# matchbox_cpu_v10.net
KiCad netlist of a schematic drawn in EAGLE
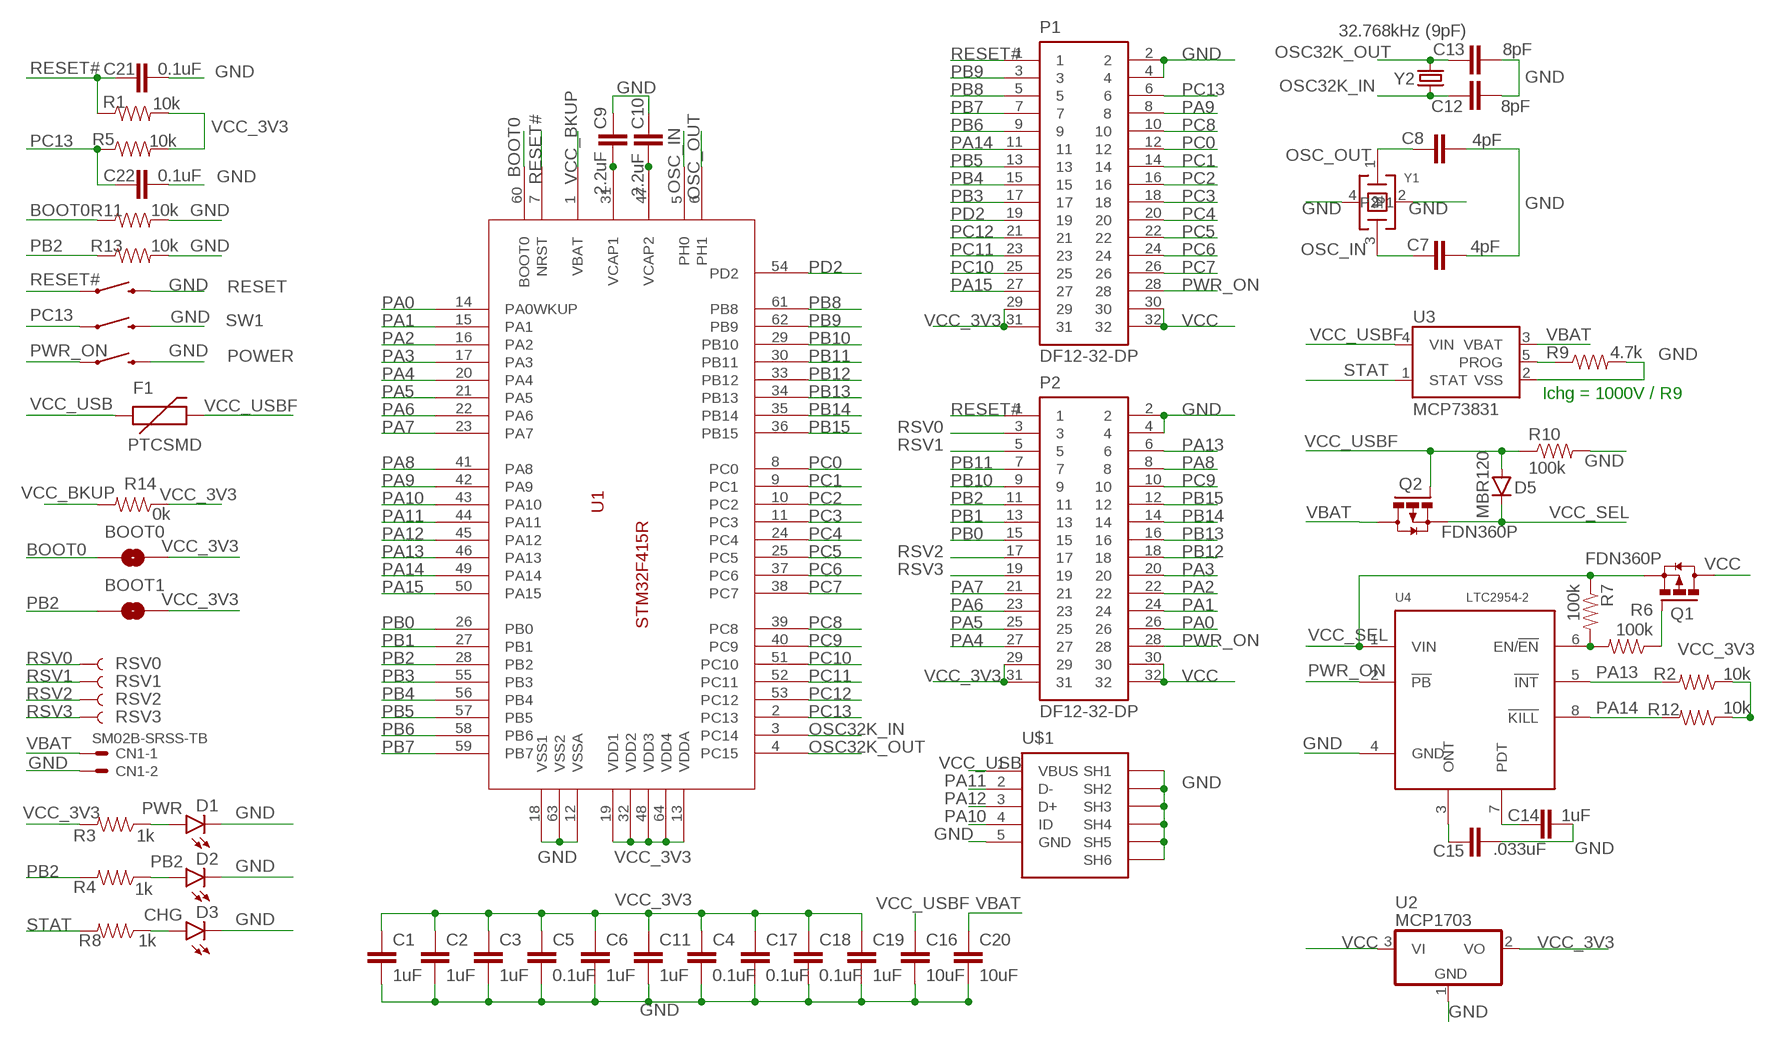
[diagram p0: schematic, sheet 1]

(export (version "E")
  (design (tool "Eeschema 10.0.6"))
  (components
    (comp (ref "BOOT0")
      (value "JUMPER-PAD-2-NOYES_SILK")
      (footprint "eagle-import:PAD-JUMPER-2-NO_YES_SILK")
      (libsource (lib "eagle-import") (part "JUMPER-PAD-2-NOYES_SILK"))
    )
    (comp (ref "BOOT1")
      (value "JUMPER-PAD-2-NOYES_SILK")
      (footprint "eagle-import:PAD-JUMPER-2-NO_YES_SILK")
      (libsource (lib "eagle-import") (part "JUMPER-PAD-2-NOYES_SILK"))
    )
    (comp (ref "C1")
      (value "1uF")
      (footprint "eagle-import:0805")
      (libsource (lib "eagle-import") (part "CAP0805"))
    )
    (comp (ref "C2")
      (value "1uF")
      (footprint "eagle-import:0805")
      (libsource (lib "eagle-import") (part "CAP0805"))
    )
    (comp (ref "C3")
      (value "1uF")
      (footprint "eagle-import:0805")
      (libsource (lib "eagle-import") (part "CAP0805"))
    )
    (comp (ref "C4")
      (value "0.1uF")
      (footprint "eagle-import:0805")
      (libsource (lib "eagle-import") (part "CAP0805"))
    )
    (comp (ref "C5")
      (value "0.1uF")
      (footprint "eagle-import:0805")
      (libsource (lib "eagle-import") (part "CAP0805"))
    )
    (comp (ref "C6")
      (value "1uF")
      (footprint "eagle-import:0805")
      (libsource (lib "eagle-import") (part "CAP0805"))
    )
    (comp (ref "C7")
      (value "4pF")
      (footprint "eagle-import:0805")
      (libsource (lib "eagle-import") (part "CAP0805"))
    )
    (comp (ref "C8")
      (value "4pF")
      (footprint "eagle-import:0805")
      (libsource (lib "eagle-import") (part "CAP0805"))
    )
    (comp (ref "C9")
      (value "2.2uF")
      (footprint "eagle-import:0805")
      (libsource (lib "eagle-import") (part "CAP0805"))
    )
    (comp (ref "C10")
      (value "2.2uF")
      (footprint "eagle-import:0805")
      (libsource (lib "eagle-import") (part "CAP0805"))
    )
    (comp (ref "C11")
      (value "1uF")
      (footprint "eagle-import:0805")
      (libsource (lib "eagle-import") (part "CAP0805"))
    )
    (comp (ref "C12")
      (value "8pF")
      (footprint "eagle-import:0402-CAP")
      (libsource (lib "eagle-import") (part "CAP0402-CAP"))
    )
    (comp (ref "C13")
      (value "8pF")
      (footprint "eagle-import:0402-CAP")
      (libsource (lib "eagle-import") (part "CAP0402-CAP"))
    )
    (comp (ref "C14")
      (value "1uF")
      (footprint "eagle-import:0805")
      (libsource (lib "eagle-import") (part "CAP0805"))
    )
    (comp (ref "C15")
      (value ".033uF")
      (footprint "eagle-import:0805")
      (libsource (lib "eagle-import") (part "CAP0805"))
    )
    (comp (ref "C16")
      (value "10uF")
      (footprint "eagle-import:0805")
      (libsource (lib "eagle-import") (part "CAP0805"))
    )
    (comp (ref "C17")
      (value "0.1uF")
      (footprint "eagle-import:0805")
      (libsource (lib "eagle-import") (part "CAP0805"))
    )
    (comp (ref "C18")
      (value "0.1uF")
      (footprint "eagle-import:0805")
      (libsource (lib "eagle-import") (part "CAP0805"))
    )
    (comp (ref "C19")
      (value "1uF")
      (footprint "eagle-import:0805")
      (libsource (lib "eagle-import") (part "CAP0805"))
    )
    (comp (ref "C20")
      (value "10uF")
      (footprint "eagle-import:0805")
      (libsource (lib "eagle-import") (part "CAP0805"))
    )
    (comp (ref "C21")
      (value "0.1uF")
      (footprint "eagle-import:0805")
      (libsource (lib "eagle-import") (part "CAP0805"))
    )
    (comp (ref "C22")
      (value "0.1uF")
      (footprint "eagle-import:0805")
      (libsource (lib "eagle-import") (part "CAP0805"))
    )
    (comp (ref "CN1")
      (value "SM02B-SRSS-TB")
      (footprint "eagle-import:SM02B-SRSS-TB")
      (libsource (lib "eagle-import") (part "?M02B-SRSS-TBS"))
    )
    (comp (ref "D1")
      (value "PWR")
      (footprint "eagle-import:LED-0603")
      (libsource (lib "eagle-import") (part "LED0603"))
    )
    (comp (ref "D2")
      (value "PB2")
      (footprint "eagle-import:LED-0603")
      (libsource (lib "eagle-import") (part "LED0603"))
    )
    (comp (ref "D3")
      (value "CHG")
      (footprint "eagle-import:LED-0603")
      (libsource (lib "eagle-import") (part "LED0603"))
    )
    (comp (ref "D5")
      (value "MBR120")
      (footprint "eagle-import:SOD-123")
      (libsource (lib "eagle-import") (part "DIODESOD123"))
    )
    (comp (ref "F1")
      (value "PTCSMD")
      (footprint "eagle-import:PTC-1206")
      (libsource (lib "eagle-import") (part "PTCSMD"))
    )
    (comp (ref "P1")
      (value "DF12-32-DP")
      (footprint "eagle-import:DF12-32-DP")
      (fields (field (name "PARTNO") "AS-ITM-00015"))
      (libsource (lib "eagle-import") (part "AS-ITM-00015"))
    )
    (comp (ref "P2")
      (value "DF12-32-DP")
      (footprint "eagle-import:DF12-32-DP")
      (fields (field (name "PARTNO") "AS-ITM-00015"))
      (libsource (lib "eagle-import") (part "AS-ITM-00015"))
    )
    (comp (ref "POWER")
      (value "SWITCH-MOMENTARY-2SMD-REDUNDANT")
      (footprint "eagle-import:TACTILE-SWITCH-SMD")
      (libsource (lib "eagle-import") (part "SWITCH-MOMENTARY-2SMD-REDUNDANT"))
    )
    (comp (ref "Q1")
      (value "FDN360P")
      (footprint "eagle-import:SUPER-SOT3")
      (libsource (lib "eagle-import") (part "FDN360P"))
    )
    (comp (ref "Q2")
      (value "FDN360P")
      (footprint "eagle-import:SUPER-SOT3")
      (libsource (lib "eagle-import") (part "FDN360P"))
    )
    (comp (ref "R1")
      (value "10k")
      (footprint "eagle-import:0805")
      (libsource (lib "eagle-import") (part "RESISTOR0805-RES"))
    )
    (comp (ref "R2")
      (value "10k")
      (footprint "eagle-import:0805")
      (libsource (lib "eagle-import") (part "RESISTOR0805-RES"))
    )
    (comp (ref "R3")
      (value "1k")
      (footprint "eagle-import:0805")
      (libsource (lib "eagle-import") (part "RESISTOR0805-RES"))
    )
    (comp (ref "R4")
      (value "1k")
      (footprint "eagle-import:0805")
      (libsource (lib "eagle-import") (part "RESISTOR0805-RES"))
    )
    (comp (ref "R5")
      (value "10k")
      (footprint "eagle-import:0805")
      (libsource (lib "eagle-import") (part "RESISTOR0805-RES"))
    )
    (comp (ref "R6")
      (value "100k")
      (footprint "eagle-import:0805")
      (libsource (lib "eagle-import") (part "RESISTOR0805-RES"))
    )
    (comp (ref "R7")
      (value "100k")
      (footprint "eagle-import:0805")
      (libsource (lib "eagle-import") (part "RESISTOR0805-RES"))
    )
    (comp (ref "R8")
      (value "1k")
      (footprint "eagle-import:0805")
      (libsource (lib "eagle-import") (part "RESISTOR0805-RES"))
    )
    (comp (ref "R9")
      (value "4.7k")
      (footprint "eagle-import:0805")
      (libsource (lib "eagle-import") (part "RESISTOR0805-RES"))
    )
    (comp (ref "R10")
      (value "100k")
      (footprint "eagle-import:0805")
      (libsource (lib "eagle-import") (part "RESISTOR0805-RES"))
    )
    (comp (ref "R11")
      (value "10k")
      (footprint "eagle-import:0805")
      (libsource (lib "eagle-import") (part "RESISTOR0805-RES"))
    )
    (comp (ref "R12")
      (value "10k")
      (footprint "eagle-import:0805")
      (libsource (lib "eagle-import") (part "RESISTOR0805-RES"))
    )
    (comp (ref "R13")
      (value "10k")
      (footprint "eagle-import:0805")
      (libsource (lib "eagle-import") (part "RESISTOR0805-RES"))
    )
    (comp (ref "R14")
      (value "0k")
      (footprint "eagle-import:0805")
      (libsource (lib "eagle-import") (part "RESISTOR0805-RES"))
    )
    (comp (ref "RESET")
      (value "SWITCH-MOMENTARY-2SMD-REDUNDANT")
      (footprint "eagle-import:TACTILE-SWITCH-SMD")
      (libsource (lib "eagle-import") (part "SWITCH-MOMENTARY-2SMD-REDUNDANT"))
    )
    (comp (ref "RSV0")
      (value "TEST-POINT3")
      (footprint "eagle-import:PAD.03X.03")
      (libsource (lib "eagle-import") (part "TEST-POINT3"))
    )
    (comp (ref "RSV1")
      (value "TEST-POINT3")
      (footprint "eagle-import:PAD.03X.03")
      (libsource (lib "eagle-import") (part "TEST-POINT3"))
    )
    (comp (ref "RSV2")
      (value "TEST-POINT3")
      (footprint "eagle-import:PAD.03X.03")
      (libsource (lib "eagle-import") (part "TEST-POINT3"))
    )
    (comp (ref "RSV3")
      (value "TEST-POINT3")
      (footprint "eagle-import:PAD.03X.03")
      (libsource (lib "eagle-import") (part "TEST-POINT3"))
    )
    (comp (ref "SW1")
      (value "SWITCH-MOMENTARY-2SMD-REDUNDANT")
      (footprint "eagle-import:TACTILE-SWITCH-SMD")
      (libsource (lib "eagle-import") (part "SWITCH-MOMENTARY-2SMD-REDUNDANT"))
    )
    (comp (ref "U$1")
      (value "MICROUSB")
      (footprint "eagle-import:MICROUSB")
      (libsource (lib "eagle-import") (part "MICROUSB"))
    )
    (comp (ref "U1")
      (value "STM32F415R")
      (footprint "eagle-import:LQFP64")
      (libsource (lib "eagle-import") (part "STM32F4R_64PIN_FOXCAR"))
    )
    (comp (ref "U2")
      (value "MCP1703")
      (footprint "eagle-import:SOT23A")
      (libsource (lib "eagle-import") (part "MCP1703"))
    )
    (comp (ref "U3")
      (value "MCP73831")
      (footprint "eagle-import:SOT23-5")
      (libsource (lib "eagle-import") (part "MCP73831"))
    )
    (comp (ref "U4")
      (value "LTC2954-2")
      (footprint "eagle-import:SOT23-8")
      (libsource (lib "eagle-import") (part "LTC2954"))
    )
    (comp (ref "Y1")
      (value "16MHz(9pF)")
      (footprint "eagle-import:ABM11")
      (fields (field (name "PARTNO") "AS-ITM-00228"))
      (libsource (lib "eagle-import") (part "AS-ITM-00228"))
    )
    (comp (ref "Y2")
      (value "32.768kHz (9pF)")
      (footprint "eagle-import:CRYSTAL-32KHZ-SMD_EPSON_MC146")
      (libsource (lib "eagle-import") (part "CRYSTALEPSONMC146"))
    )
  )
  (nets
    (net (code "1") (name "/BOOT0") (class "Default")
      (node (ref "BOOT0") (pin "1") (pinfunction "1_1") (pintype "passive"))
      (node (ref "R11") (pin "1") (pinfunction "1_1") (pintype "passive"))
      (node (ref "U1") (pin "60") (pinfunction "BOOT0_60") (pintype "input"))
    )
    (net (code "2") (name "/GND") (class "Default")
      (node (ref "C1") (pin "2") (pinfunction "2_2") (pintype "passive"))
      (node (ref "C10") (pin "1") (pinfunction "1_1") (pintype "passive"))
      (node (ref "C11") (pin "2") (pinfunction "2_2") (pintype "passive"))
      (node (ref "C12") (pin "2") (pinfunction "2_2") (pintype "passive"))
      (node (ref "C13") (pin "2") (pinfunction "2_2") (pintype "passive"))
      (node (ref "C14") (pin "2") (pinfunction "2_2") (pintype "passive"))
      (node (ref "C15") (pin "2") (pinfunction "2_2") (pintype "passive"))
      (node (ref "C16") (pin "2") (pinfunction "2_2") (pintype "passive"))
      (node (ref "C17") (pin "2") (pinfunction "2_2") (pintype "passive"))
      (node (ref "C18") (pin "2") (pinfunction "2_2") (pintype "passive"))
      (node (ref "C19") (pin "2") (pinfunction "2_2") (pintype "passive"))
      (node (ref "C2") (pin "2") (pinfunction "2_2") (pintype "passive"))
      (node (ref "C20") (pin "2") (pinfunction "2_2") (pintype "passive"))
      (node (ref "C21") (pin "2") (pinfunction "2_2") (pintype "passive"))
      (node (ref "C22") (pin "2") (pinfunction "2_2") (pintype "passive"))
      (node (ref "C3") (pin "2") (pinfunction "2_2") (pintype "passive"))
      (node (ref "C4") (pin "2") (pinfunction "2_2") (pintype "passive"))
      (node (ref "C5") (pin "2") (pinfunction "2_2") (pintype "passive"))
      (node (ref "C6") (pin "2") (pinfunction "2_2") (pintype "passive"))
      (node (ref "C7") (pin "2") (pinfunction "2_2") (pintype "passive"))
      (node (ref "C8") (pin "2") (pinfunction "2_2") (pintype "passive"))
      (node (ref "C9") (pin "1") (pinfunction "1_1") (pintype "passive"))
      (node (ref "CN1") (pin "2") (pinfunction "S_2") (pintype "passive"))
      (node (ref "D1") (pin "C") (pinfunction "C_C") (pintype "passive"))
      (node (ref "D2") (pin "C") (pinfunction "C_C") (pintype "passive"))
      (node (ref "D3") (pin "C") (pinfunction "C_C") (pintype "passive"))
      (node (ref "P1") (pin "2") (pinfunction "2_2") (pintype "bidirectional"))
      (node (ref "P1") (pin "4") (pinfunction "4_4") (pintype "bidirectional"))
      (node (ref "P2") (pin "2") (pinfunction "2_2") (pintype "bidirectional"))
      (node (ref "P2") (pin "4") (pinfunction "4_4") (pintype "bidirectional"))
      (node (ref "POWER") (pin "3") (pinfunction "2_3") (pintype "passive"))
      (node (ref "POWER") (pin "4") (pinfunction "2_4") (pintype "passive"))
      (node (ref "R10") (pin "2") (pinfunction "2_2") (pintype "passive"))
      (node (ref "R11") (pin "2") (pinfunction "2_2") (pintype "passive"))
      (node (ref "R13") (pin "2") (pinfunction "2_2") (pintype "passive"))
      (node (ref "R9") (pin "2") (pinfunction "2_2") (pintype "passive"))
      (node (ref "RESET") (pin "3") (pinfunction "2_3") (pintype "passive"))
      (node (ref "RESET") (pin "4") (pinfunction "2_4") (pintype "passive"))
      (node (ref "SW1") (pin "3") (pinfunction "2_3") (pintype "passive"))
      (node (ref "SW1") (pin "4") (pinfunction "2_4") (pintype "passive"))
      (node (ref "U$1") (pin "10") (pinfunction "SH5_10") (pintype "bidirectional"))
      (node (ref "U$1") (pin "11") (pinfunction "SH6_11") (pintype "bidirectional"))
      (node (ref "U$1") (pin "5") (pinfunction "GND_5") (pintype "bidirectional"))
      (node (ref "U$1") (pin "6") (pinfunction "SH1_6") (pintype "bidirectional"))
      (node (ref "U$1") (pin "7") (pinfunction "SH2_7") (pintype "bidirectional"))
      (node (ref "U$1") (pin "8") (pinfunction "SH3_8") (pintype "bidirectional"))
      (node (ref "U$1") (pin "9") (pinfunction "SH4_9") (pintype "bidirectional"))
      (node (ref "U1") (pin "12") (pinfunction "VSSA_12") (pintype "input"))
      (node (ref "U1") (pin "18") (pinfunction "VSS1_18") (pintype "input"))
      (node (ref "U1") (pin "63") (pinfunction "VSS2_63") (pintype "input"))
      (node (ref "U2") (pin "1") (pinfunction "GND_1") (pintype "passive"))
      (node (ref "U3") (pin "2") (pinfunction "VSS_2") (pintype "power_in"))
      (node (ref "U4") (pin "4") (pinfunction "GND_4") (pintype "power_in"))
      (node (ref "Y1") (pin "2") (pinfunction "P2_2") (pintype "bidirectional"))
      (node (ref "Y1") (pin "4") (pinfunction "P1_4") (pintype "bidirectional"))
    )
    (net (code "3") (name "/OSC32K_IN") (class "Default")
      (node (ref "C12") (pin "1") (pinfunction "1_1") (pintype "passive"))
      (node (ref "U1") (pin "3") (pinfunction "PC14_3") (pintype "bidirectional"))
      (node (ref "Y2") (pin "P$2") (pinfunction "1_P$2") (pintype "passive"))
    )
    (net (code "4") (name "/OSC32K_OUT") (class "Default")
      (node (ref "C13") (pin "1") (pinfunction "1_1") (pintype "passive"))
      (node (ref "U1") (pin "4") (pinfunction "PC15_4") (pintype "bidirectional"))
      (node (ref "Y2") (pin "P$1") (pinfunction "2_P$1") (pintype "passive"))
    )
    (net (code "5") (name "/OSC_IN") (class "Default")
      (node (ref "C7") (pin "1") (pinfunction "1_1") (pintype "passive"))
      (node (ref "U1") (pin "5") (pinfunction "PH0_5") (pintype "bidirectional"))
      (node (ref "Y1") (pin "3") (pinfunction "2_3") (pintype "bidirectional"))
    )
    (net (code "6") (name "/OSC_OUT") (class "Default")
      (node (ref "C8") (pin "1") (pinfunction "1_1") (pintype "passive"))
      (node (ref "U1") (pin "6") (pinfunction "PH1_6") (pintype "bidirectional"))
      (node (ref "Y1") (pin "1") (pinfunction "1_1") (pintype "bidirectional"))
    )
    (net (code "7") (name "/PA0") (class "Default")
      (node (ref "P2") (pin "26") (pinfunction "26_26") (pintype "bidirectional"))
      (node (ref "U1") (pin "14") (pinfunction "PA0WKUP_14") (pintype "bidirectional"))
    )
    (net (code "8") (name "/PA1") (class "Default")
      (node (ref "P2") (pin "24") (pinfunction "24_24") (pintype "bidirectional"))
      (node (ref "U1") (pin "15") (pinfunction "PA1_15") (pintype "bidirectional"))
    )
    (net (code "9") (name "/PA2") (class "Default")
      (node (ref "P2") (pin "22") (pinfunction "22_22") (pintype "bidirectional"))
      (node (ref "U1") (pin "16") (pinfunction "PA2_16") (pintype "bidirectional"))
    )
    (net (code "10") (name "/PA3") (class "Default")
      (node (ref "P2") (pin "20") (pinfunction "20_20") (pintype "bidirectional"))
      (node (ref "U1") (pin "17") (pinfunction "PA3_17") (pintype "bidirectional"))
    )
    (net (code "11") (name "/PA4") (class "Default")
      (node (ref "P2") (pin "27") (pinfunction "27_27") (pintype "bidirectional"))
      (node (ref "U1") (pin "20") (pinfunction "PA4_20") (pintype "bidirectional"))
    )
    (net (code "12") (name "/PA5") (class "Default")
      (node (ref "P2") (pin "25") (pinfunction "25_25") (pintype "bidirectional"))
      (node (ref "U1") (pin "21") (pinfunction "PA5_21") (pintype "bidirectional"))
    )
    (net (code "13") (name "/PA6") (class "Default")
      (node (ref "P2") (pin "23") (pinfunction "23_23") (pintype "bidirectional"))
      (node (ref "U1") (pin "22") (pinfunction "PA6_22") (pintype "bidirectional"))
    )
    (net (code "14") (name "/PA7") (class "Default")
      (node (ref "P2") (pin "21") (pinfunction "21_21") (pintype "bidirectional"))
      (node (ref "U1") (pin "23") (pinfunction "PA7_23") (pintype "bidirectional"))
    )
    (net (code "15") (name "/PA8") (class "Default")
      (node (ref "P2") (pin "8") (pinfunction "8_8") (pintype "bidirectional"))
      (node (ref "U1") (pin "41") (pinfunction "PA8_41") (pintype "bidirectional"))
    )
    (net (code "16") (name "/PA9") (class "Default")
      (node (ref "P1") (pin "8") (pinfunction "8_8") (pintype "bidirectional"))
      (node (ref "U1") (pin "42") (pinfunction "PA9_42") (pintype "bidirectional"))
    )
    (net (code "17") (name "/PA10") (class "Default")
      (node (ref "U$1") (pin "4") (pinfunction "ID_4") (pintype "bidirectional"))
      (node (ref "U1") (pin "43") (pinfunction "PA10_43") (pintype "bidirectional"))
    )
    (net (code "18") (name "/PA11") (class "Default")
      (node (ref "U$1") (pin "2") (pinfunction "D-_2") (pintype "bidirectional"))
      (node (ref "U1") (pin "44") (pinfunction "PA11_44") (pintype "bidirectional"))
    )
    (net (code "19") (name "/PA12") (class "Default")
      (node (ref "U$1") (pin "3") (pinfunction "D+_3") (pintype "bidirectional"))
      (node (ref "U1") (pin "45") (pinfunction "PA12_45") (pintype "bidirectional"))
    )
    (net (code "20") (name "/PA13") (class "Default")
      (node (ref "P2") (pin "6") (pinfunction "6_6") (pintype "bidirectional"))
      (node (ref "R2") (pin "2") (pinfunction "2_2") (pintype "passive"))
      (node (ref "U1") (pin "46") (pinfunction "PA13_46") (pintype "bidirectional"))
      (node (ref "U4") (pin "5") (pinfunction "~{INT}_5") (pintype "output"))
    )
    (net (code "21") (name "/PA14") (class "Default")
      (node (ref "P1") (pin "11") (pinfunction "11_11") (pintype "bidirectional"))
      (node (ref "R12") (pin "2") (pinfunction "2_2") (pintype "passive"))
      (node (ref "U1") (pin "49") (pinfunction "PA14_49") (pintype "bidirectional"))
      (node (ref "U4") (pin "8") (pinfunction "~{KILL}_8") (pintype "input"))
    )
    (net (code "22") (name "/PA15") (class "Default")
      (node (ref "P1") (pin "27") (pinfunction "27_27") (pintype "bidirectional"))
      (node (ref "U1") (pin "50") (pinfunction "PA15_50") (pintype "bidirectional"))
    )
    (net (code "23") (name "/PB0") (class "Default")
      (node (ref "P2") (pin "15") (pinfunction "15_15") (pintype "bidirectional"))
      (node (ref "U1") (pin "26") (pinfunction "PB0_26") (pintype "bidirectional"))
    )
    (net (code "24") (name "/PB1") (class "Default")
      (node (ref "P2") (pin "13") (pinfunction "13_13") (pintype "bidirectional"))
      (node (ref "U1") (pin "27") (pinfunction "PB1_27") (pintype "bidirectional"))
    )
    (net (code "25") (name "/PB2") (class "Default")
      (node (ref "BOOT1") (pin "1") (pinfunction "1_1") (pintype "passive"))
      (node (ref "P2") (pin "11") (pinfunction "11_11") (pintype "bidirectional"))
      (node (ref "R13") (pin "1") (pinfunction "1_1") (pintype "passive"))
      (node (ref "R4") (pin "2") (pinfunction "2_2") (pintype "passive"))
      (node (ref "U1") (pin "28") (pinfunction "PB2_28") (pintype "bidirectional"))
    )
    (net (code "26") (name "/PB3") (class "Default")
      (node (ref "P1") (pin "17") (pinfunction "17_17") (pintype "bidirectional"))
      (node (ref "U1") (pin "55") (pinfunction "PB3_55") (pintype "bidirectional"))
    )
    (net (code "27") (name "/PB4") (class "Default")
      (node (ref "P1") (pin "15") (pinfunction "15_15") (pintype "bidirectional"))
      (node (ref "U1") (pin "56") (pinfunction "PB4_56") (pintype "bidirectional"))
    )
    (net (code "28") (name "/PB5") (class "Default")
      (node (ref "P1") (pin "13") (pinfunction "13_13") (pintype "bidirectional"))
      (node (ref "U1") (pin "57") (pinfunction "PB5_57") (pintype "bidirectional"))
    )
    (net (code "29") (name "/PB6") (class "Default")
      (node (ref "P1") (pin "9") (pinfunction "9_9") (pintype "bidirectional"))
      (node (ref "U1") (pin "58") (pinfunction "PB6_58") (pintype "bidirectional"))
    )
    (net (code "30") (name "/PB7") (class "Default")
      (node (ref "P1") (pin "7") (pinfunction "7_7") (pintype "bidirectional"))
      (node (ref "U1") (pin "59") (pinfunction "PB7_59") (pintype "bidirectional"))
    )
    (net (code "31") (name "/PB8") (class "Default")
      (node (ref "P1") (pin "5") (pinfunction "5_5") (pintype "bidirectional"))
      (node (ref "U1") (pin "61") (pinfunction "PB8_61") (pintype "bidirectional"))
    )
    (net (code "32") (name "/PB9") (class "Default")
      (node (ref "P1") (pin "3") (pinfunction "3_3") (pintype "bidirectional"))
      (node (ref "U1") (pin "62") (pinfunction "PB9_62") (pintype "bidirectional"))
    )
    (net (code "33") (name "/PB10") (class "Default")
      (node (ref "P2") (pin "9") (pinfunction "9_9") (pintype "bidirectional"))
      (node (ref "U1") (pin "29") (pinfunction "PB10_29") (pintype "bidirectional"))
    )
    (net (code "34") (name "/PB11") (class "Default")
      (node (ref "P2") (pin "7") (pinfunction "7_7") (pintype "bidirectional"))
      (node (ref "U1") (pin "30") (pinfunction "PB11_30") (pintype "bidirectional"))
    )
    (net (code "35") (name "/PB12") (class "Default")
      (node (ref "P2") (pin "18") (pinfunction "18_18") (pintype "bidirectional"))
      (node (ref "U1") (pin "33") (pinfunction "PB12_33") (pintype "bidirectional"))
    )
    (net (code "36") (name "/PB13") (class "Default")
      (node (ref "P2") (pin "16") (pinfunction "16_16") (pintype "bidirectional"))
      (node (ref "U1") (pin "34") (pinfunction "PB13_34") (pintype "bidirectional"))
    )
    (net (code "37") (name "/PB14") (class "Default")
      (node (ref "P2") (pin "14") (pinfunction "14_14") (pintype "bidirectional"))
      (node (ref "U1") (pin "35") (pinfunction "PB14_35") (pintype "bidirectional"))
    )
    (net (code "38") (name "/PB15") (class "Default")
      (node (ref "P2") (pin "12") (pinfunction "12_12") (pintype "bidirectional"))
      (node (ref "U1") (pin "36") (pinfunction "PB15_36") (pintype "bidirectional"))
    )
    (net (code "39") (name "/PC0") (class "Default")
      (node (ref "P1") (pin "12") (pinfunction "12_12") (pintype "bidirectional"))
      (node (ref "U1") (pin "8") (pinfunction "PC0_8") (pintype "bidirectional"))
    )
    (net (code "40") (name "/PC1") (class "Default")
      (node (ref "P1") (pin "14") (pinfunction "14_14") (pintype "bidirectional"))
      (node (ref "U1") (pin "9") (pinfunction "PC1_9") (pintype "bidirectional"))
    )
    (net (code "41") (name "/PC2") (class "Default")
      (node (ref "P1") (pin "16") (pinfunction "16_16") (pintype "bidirectional"))
      (node (ref "U1") (pin "10") (pinfunction "PC2_10") (pintype "bidirectional"))
    )
    (net (code "42") (name "/PC3") (class "Default")
      (node (ref "P1") (pin "18") (pinfunction "18_18") (pintype "bidirectional"))
      (node (ref "U1") (pin "11") (pinfunction "PC3_11") (pintype "bidirectional"))
    )
    (net (code "43") (name "/PC4") (class "Default")
      (node (ref "P1") (pin "20") (pinfunction "20_20") (pintype "bidirectional"))
      (node (ref "U1") (pin "24") (pinfunction "PC4_24") (pintype "bidirectional"))
    )
    (net (code "44") (name "/PC5") (class "Default")
      (node (ref "P1") (pin "22") (pinfunction "22_22") (pintype "bidirectional"))
      (node (ref "U1") (pin "25") (pinfunction "PC5_25") (pintype "bidirectional"))
    )
    (net (code "45") (name "/PC6") (class "Default")
      (node (ref "P1") (pin "24") (pinfunction "24_24") (pintype "bidirectional"))
      (node (ref "U1") (pin "37") (pinfunction "PC6_37") (pintype "bidirectional"))
    )
    (net (code "46") (name "/PC7") (class "Default")
      (node (ref "P1") (pin "26") (pinfunction "26_26") (pintype "bidirectional"))
      (node (ref "U1") (pin "38") (pinfunction "PC7_38") (pintype "bidirectional"))
    )
    (net (code "47") (name "/PC8") (class "Default")
      (node (ref "P1") (pin "10") (pinfunction "10_10") (pintype "bidirectional"))
      (node (ref "U1") (pin "39") (pinfunction "PC8_39") (pintype "bidirectional"))
    )
    (net (code "48") (name "/PC9") (class "Default")
      (node (ref "P2") (pin "10") (pinfunction "10_10") (pintype "bidirectional"))
      (node (ref "U1") (pin "40") (pinfunction "PC9_40") (pintype "bidirectional"))
    )
    (net (code "49") (name "/PC10") (class "Default")
      (node (ref "P1") (pin "25") (pinfunction "25_25") (pintype "bidirectional"))
      (node (ref "U1") (pin "51") (pinfunction "PC10_51") (pintype "bidirectional"))
    )
    (net (code "50") (name "/PC11") (class "Default")
      (node (ref "P1") (pin "23") (pinfunction "23_23") (pintype "bidirectional"))
      (node (ref "U1") (pin "52") (pinfunction "PC11_52") (pintype "bidirectional"))
    )
    (net (code "51") (name "/PC12") (class "Default")
      (node (ref "P1") (pin "21") (pinfunction "21_21") (pintype "bidirectional"))
      (node (ref "U1") (pin "53") (pinfunction "PC12_53") (pintype "bidirectional"))
    )
    (net (code "52") (name "/PC13") (class "Default")
      (node (ref "C22") (pin "1") (pinfunction "1_1") (pintype "passive"))
      (node (ref "P1") (pin "6") (pinfunction "6_6") (pintype "bidirectional"))
      (node (ref "R5") (pin "1") (pinfunction "1_1") (pintype "passive"))
      (node (ref "SW1") (pin "1") (pinfunction "1_1") (pintype "passive"))
      (node (ref "SW1") (pin "2") (pinfunction "1_2") (pintype "passive"))
      (node (ref "U1") (pin "2") (pinfunction "PC13_2") (pintype "bidirectional"))
    )
    (net (code "53") (name "/PD2") (class "Default")
      (node (ref "P1") (pin "19") (pinfunction "19_19") (pintype "bidirectional"))
      (node (ref "U1") (pin "54") (pinfunction "PD2_54") (pintype "bidirectional"))
    )
    (net (code "54") (name "/PWR_ON") (class "Default")
      (node (ref "P1") (pin "28") (pinfunction "28_28") (pintype "bidirectional"))
      (node (ref "P2") (pin "28") (pinfunction "28_28") (pintype "bidirectional"))
      (node (ref "POWER") (pin "1") (pinfunction "1_1") (pintype "passive"))
      (node (ref "POWER") (pin "2") (pinfunction "1_2") (pintype "passive"))
      (node (ref "U4") (pin "2") (pinfunction "~{PB}_2") (pintype "passive"))
    )
    (net (code "55") (name "/RESET#") (class "Default")
      (node (ref "C21") (pin "1") (pinfunction "1_1") (pintype "passive"))
      (node (ref "P1") (pin "1") (pinfunction "1_1") (pintype "bidirectional"))
      (node (ref "P2") (pin "1") (pinfunction "1_1") (pintype "bidirectional"))
      (node (ref "R1") (pin "1") (pinfunction "1_1") (pintype "passive"))
      (node (ref "RESET") (pin "1") (pinfunction "1_1") (pintype "passive"))
      (node (ref "RESET") (pin "2") (pinfunction "1_2") (pintype "passive"))
      (node (ref "U1") (pin "7") (pinfunction "NRST_7") (pintype "input"))
    )
    (net (code "56") (name "/RSV0") (class "Default")
      (node (ref "P2") (pin "3") (pinfunction "3_3") (pintype "bidirectional"))
      (node (ref "RSV0") (pin "P$1") (pinfunction "1_P$1") (pintype "bidirectional"))
    )
    (net (code "57") (name "/RSV1") (class "Default")
      (node (ref "P2") (pin "5") (pinfunction "5_5") (pintype "bidirectional"))
      (node (ref "RSV1") (pin "P$1") (pinfunction "1_P$1") (pintype "bidirectional"))
    )
    (net (code "58") (name "/RSV2") (class "Default")
      (node (ref "P2") (pin "17") (pinfunction "17_17") (pintype "bidirectional"))
      (node (ref "RSV2") (pin "P$1") (pinfunction "1_P$1") (pintype "bidirectional"))
    )
    (net (code "59") (name "/RSV3") (class "Default")
      (node (ref "P2") (pin "19") (pinfunction "19_19") (pintype "bidirectional"))
      (node (ref "RSV3") (pin "P$1") (pinfunction "1_P$1") (pintype "bidirectional"))
    )
    (net (code "60") (name "/STAT") (class "Default")
      (node (ref "R8") (pin "2") (pinfunction "2_2") (pintype "passive"))
      (node (ref "U3") (pin "1") (pinfunction "STAT_1") (pintype "output"))
    )
    (net (code "61") (name "/VBAT") (class "Default")
      (node (ref "C20") (pin "1") (pinfunction "1_1") (pintype "passive"))
      (node (ref "CN1") (pin "1") (pinfunction "S_1") (pintype "passive"))
      (node (ref "Q2") (pin "3") (pinfunction "D_3") (pintype "passive"))
      (node (ref "U3") (pin "3") (pinfunction "VBAT_3") (pintype "power_in"))
    )
    (net (code "62") (name "/VCC") (class "Default")
      (node (ref "P1") (pin "30") (pinfunction "30_30") (pintype "bidirectional"))
      (node (ref "P1") (pin "32") (pinfunction "32_32") (pintype "bidirectional"))
      (node (ref "P2") (pin "30") (pinfunction "30_30") (pintype "bidirectional"))
      (node (ref "P2") (pin "32") (pinfunction "32_32") (pintype "bidirectional"))
      (node (ref "Q1") (pin "3") (pinfunction "D_3") (pintype "passive"))
      (node (ref "U2") (pin "3") (pinfunction "VI_3") (pintype "input"))
    )
    (net (code "63") (name "/VCC_3V3") (class "Default")
      (node (ref "BOOT0") (pin "2") (pinfunction "2_2") (pintype "passive"))
      (node (ref "BOOT1") (pin "2") (pinfunction "2_2") (pintype "passive"))
      (node (ref "C1") (pin "1") (pinfunction "1_1") (pintype "passive"))
      (node (ref "C11") (pin "1") (pinfunction "1_1") (pintype "passive"))
      (node (ref "C17") (pin "1") (pinfunction "1_1") (pintype "passive"))
      (node (ref "C18") (pin "1") (pinfunction "1_1") (pintype "passive"))
      (node (ref "C19") (pin "1") (pinfunction "1_1") (pintype "passive"))
      (node (ref "C2") (pin "1") (pinfunction "1_1") (pintype "passive"))
      (node (ref "C3") (pin "1") (pinfunction "1_1") (pintype "passive"))
      (node (ref "C4") (pin "1") (pinfunction "1_1") (pintype "passive"))
      (node (ref "C5") (pin "1") (pinfunction "1_1") (pintype "passive"))
      (node (ref "C6") (pin "1") (pinfunction "1_1") (pintype "passive"))
      (node (ref "P1") (pin "29") (pinfunction "29_29") (pintype "bidirectional"))
      (node (ref "P1") (pin "31") (pinfunction "31_31") (pintype "bidirectional"))
      (node (ref "P2") (pin "29") (pinfunction "29_29") (pintype "bidirectional"))
      (node (ref "P2") (pin "31") (pinfunction "31_31") (pintype "bidirectional"))
      (node (ref "R1") (pin "2") (pinfunction "2_2") (pintype "passive"))
      (node (ref "R12") (pin "1") (pinfunction "1_1") (pintype "passive"))
      (node (ref "R14") (pin "1") (pinfunction "1_1") (pintype "passive"))
      (node (ref "R2") (pin "1") (pinfunction "1_1") (pintype "passive"))
      (node (ref "R3") (pin "2") (pinfunction "2_2") (pintype "passive"))
      (node (ref "R5") (pin "2") (pinfunction "2_2") (pintype "passive"))
      (node (ref "U1") (pin "13") (pinfunction "VDDA_13") (pintype "power_in"))
      (node (ref "U1") (pin "19") (pinfunction "VDD1_19") (pintype "power_in"))
      (node (ref "U1") (pin "32") (pinfunction "VDD2_32") (pintype "power_in"))
      (node (ref "U1") (pin "48") (pinfunction "VDD3_48") (pintype "power_in"))
      (node (ref "U1") (pin "64") (pinfunction "VDD4_64") (pintype "power_in"))
      (node (ref "U2") (pin "2") (pinfunction "VO_2") (pintype "passive"))
    )
    (net (code "64") (name "/VCC_BKUP") (class "Default")
      (node (ref "R14") (pin "2") (pinfunction "2_2") (pintype "passive"))
      (node (ref "U1") (pin "1") (pinfunction "VBAT_1") (pintype "bidirectional"))
    )
    (net (code "65") (name "/VCC_SEL") (class "Default")
      (node (ref "D5") (pin "C") (pinfunction "C_C") (pintype "passive"))
      (node (ref "Q1") (pin "2") (pinfunction "S_2") (pintype "passive"))
      (node (ref "Q2") (pin "2") (pinfunction "S_2") (pintype "passive"))
      (node (ref "R7") (pin "1") (pinfunction "1_1") (pintype "passive"))
      (node (ref "U4") (pin "1") (pinfunction "VIN_1") (pintype "power_in"))
    )
    (net (code "66") (name "/VCC_USB") (class "Default")
      (node (ref "F1") (pin "1") (pinfunction "1_1") (pintype "bidirectional"))
      (node (ref "U$1") (pin "1") (pinfunction "VBUS_1") (pintype "bidirectional"))
    )
    (net (code "67") (name "/VCC_USBF") (class "Default")
      (node (ref "C16") (pin "1") (pinfunction "1_1") (pintype "passive"))
      (node (ref "D5") (pin "A") (pinfunction "A_A") (pintype "passive"))
      (node (ref "F1") (pin "2") (pinfunction "2_2") (pintype "bidirectional"))
      (node (ref "Q2") (pin "1") (pinfunction "G_1") (pintype "passive"))
      (node (ref "R10") (pin "1") (pinfunction "1_1") (pintype "passive"))
      (node (ref "U3") (pin "4") (pinfunction "VIN_4") (pintype "power_in"))
    )
    (net (code "68") (name "Net-(D1-PadA)") (class "Default")
      (node (ref "D1") (pin "A") (pinfunction "A_A") (pintype "passive"))
      (node (ref "R3") (pin "1") (pinfunction "1_1") (pintype "passive"))
    )
    (net (code "69") (name "Net-(D2-PadA)") (class "Default")
      (node (ref "D2") (pin "A") (pinfunction "A_A") (pintype "passive"))
      (node (ref "R4") (pin "1") (pinfunction "1_1") (pintype "passive"))
    )
    (net (code "70") (name "Net-(D3-PadA)") (class "Default")
      (node (ref "D3") (pin "A") (pinfunction "A_A") (pintype "passive"))
      (node (ref "R8") (pin "1") (pinfunction "1_1") (pintype "passive"))
    )
    (net (code "71") (name "Net-(Q1-G)") (class "Default")
      (node (ref "Q1") (pin "1") (pinfunction "G_1") (pintype "passive"))
      (node (ref "R6") (pin "1") (pinfunction "1_1") (pintype "passive"))
    )
    (net (code "72") (name "Net-(U1-VCAP1)") (class "Default")
      (node (ref "C9") (pin "2") (pinfunction "2_2") (pintype "passive"))
      (node (ref "U1") (pin "31") (pinfunction "VCAP1_31") (pintype "output"))
    )
    (net (code "73") (name "Net-(U1-VCAP2)") (class "Default")
      (node (ref "C10") (pin "2") (pinfunction "2_2") (pintype "passive"))
      (node (ref "U1") (pin "47") (pinfunction "VCAP2_47") (pintype "output"))
    )
    (net (code "74") (name "Net-(U3-PROG)") (class "Default")
      (node (ref "R9") (pin "1") (pinfunction "1_1") (pintype "passive"))
      (node (ref "U3") (pin "5") (pinfunction "PROG_5") (pintype "input"))
    )
    (net (code "75") (name "Net-(U4-EN{slash}~{EN})") (class "Default")
      (node (ref "R6") (pin "2") (pinfunction "2_2") (pintype "passive"))
      (node (ref "R7") (pin "2") (pinfunction "2_2") (pintype "passive"))
      (node (ref "U4") (pin "6") (pinfunction "EN/~{EN}_6") (pintype "output"))
    )
    (net (code "76") (name "Net-(U4-ONT)") (class "Default")
      (node (ref "C15") (pin "1") (pinfunction "1_1") (pintype "passive"))
      (node (ref "U4") (pin "3") (pinfunction "ONT_3") (pintype "passive"))
    )
    (net (code "77") (name "Net-(U4-PDT)") (class "Default")
      (node (ref "C14") (pin "1") (pinfunction "1_1") (pintype "passive"))
      (node (ref "U4") (pin "7") (pinfunction "PDT_7") (pintype "passive"))
    )
  )
)
